# Driver_mosfet_v1_4.net
KiCad netlist of a schematic drawn in EAGLE
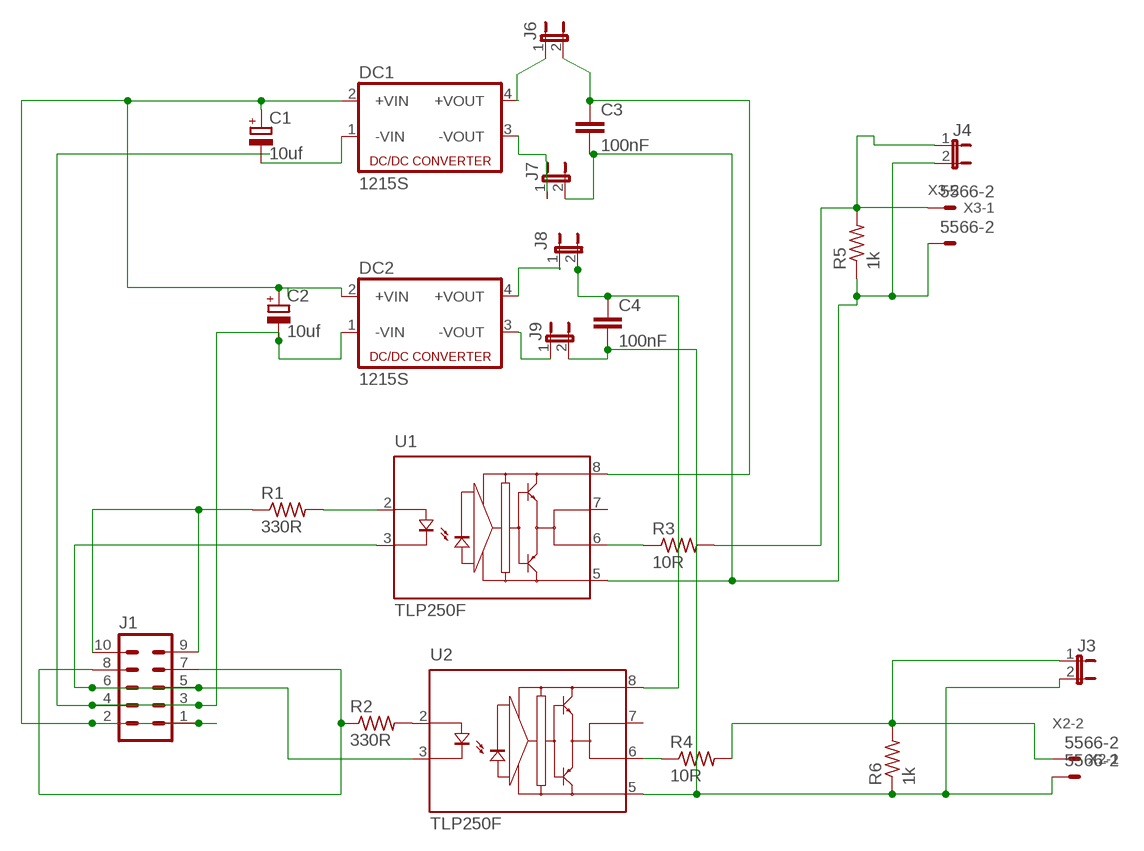
[diagram p0: schematic, sheet 1]

(export (version "E")
  (design (tool "Eeschema 10.0.6"))
  (components
    (comp (ref "C1")
      (value "10uf")
      (footprint "eagle-import:E2,5-6")
      (libsource (lib "eagle-import") (part "CPOL-EUE2.5-6"))
    )
    (comp (ref "C2")
      (value "10uf")
      (footprint "eagle-import:E2,5-6")
      (libsource (lib "eagle-import") (part "CPOL-EUE2.5-6"))
    )
    (comp (ref "C3")
      (value "100nF")
      (footprint "eagle-import:C5B3.5")
      (libsource (lib "eagle-import") (part "C5/3.5"))
    )
    (comp (ref "C4")
      (value "100nF")
      (footprint "eagle-import:C5B3.5")
      (libsource (lib "eagle-import") (part "C5/3.5"))
    )
    (comp (ref "DC1")
      (value "1215S")
      (footprint "eagle-import:4SIL")
      (libsource (lib "eagle-import") (part "VA-?S1.52409"))
    )
    (comp (ref "DC2")
      (value "1215S")
      (footprint "eagle-import:4SIL")
      (libsource (lib "eagle-import") (part "VA-?S1.52409"))
    )
    (comp (ref "J1")
      (value "MA05-2")
      (footprint "eagle-import:MA05-2")
      (libsource (lib "eagle-import") (part "MA05-2"))
    )
    (comp (ref "J3")
      (value "JP1E")
      (footprint "eagle-import:JP1")
      (libsource (lib "eagle-import") (part "JP1E"))
    )
    (comp (ref "J4")
      (value "JP1E")
      (footprint "eagle-import:JP1")
      (libsource (lib "eagle-import") (part "JP1E"))
    )
    (comp (ref "J6")
      (value "JP1E")
      (footprint "eagle-import:JP1")
      (libsource (lib "eagle-import") (part "JP1E"))
    )
    (comp (ref "J7")
      (value "JP1E")
      (footprint "eagle-import:JP1")
      (libsource (lib "eagle-import") (part "JP1E"))
    )
    (comp (ref "J8")
      (value "JP1E")
      (footprint "eagle-import:JP1")
      (libsource (lib "eagle-import") (part "JP1E"))
    )
    (comp (ref "J9")
      (value "JP1E")
      (footprint "eagle-import:JP1")
      (libsource (lib "eagle-import") (part "JP1E"))
    )
    (comp (ref "R1")
      (value "330R")
      (footprint "eagle-import:0309_12")
      (libsource (lib "eagle-import") (part "R-US_0309/12"))
    )
    (comp (ref "R2")
      (value "330R")
      (footprint "eagle-import:0309_12")
      (libsource (lib "eagle-import") (part "R-US_0309/12"))
    )
    (comp (ref "R3")
      (value "10R")
      (footprint "eagle-import:0309_12")
      (libsource (lib "eagle-import") (part "R-US_0309/12"))
    )
    (comp (ref "R4")
      (value "10R")
      (footprint "eagle-import:0309_12")
      (libsource (lib "eagle-import") (part "R-US_0309/12"))
    )
    (comp (ref "R5")
      (value "1k")
      (footprint "eagle-import:0309_12")
      (libsource (lib "eagle-import") (part "R-US_0309/12"))
    )
    (comp (ref "R6")
      (value "1k")
      (footprint "eagle-import:0309_12")
      (libsource (lib "eagle-import") (part "R-US_0309/12"))
    )
    (comp (ref "U1")
      (value "TLP250F")
      (footprint "eagle-import:DIL08")
      (libsource (lib "eagle-import") (part "TLP250F"))
    )
    (comp (ref "U2")
      (value "TLP250F")
      (footprint "eagle-import:DIL08")
      (libsource (lib "eagle-import") (part "TLP250F"))
    )
    (comp (ref "X2")
      (value "5566-2")
      (footprint "eagle-import:5566-2")
      (fields (field (name "MF") "MOLEX"))
      (libsource (lib "eagle-import") (part "5566-2"))
    )
    (comp (ref "X3")
      (value "5566-2")
      (footprint "eagle-import:5566-2")
      (fields (field (name "MF") "MOLEX"))
      (libsource (lib "eagle-import") (part "5566-2"))
    )
  )
  (nets
    (net (code "1") (name "/N$22") (class "Default")
      (node (ref "C1") (pin "-") (pinfunction "-_-") (pintype "passive"))
      (node (ref "C2") (pin "-") (pinfunction "-_-") (pintype "passive"))
      (node (ref "DC1") (pin "1") (pinfunction "-VIN_1") (pintype "passive"))
      (node (ref "DC2") (pin "1") (pinfunction "-VIN_1") (pintype "passive"))
      (node (ref "J1") (pin "3") (pinfunction "3_3") (pintype "passive"))
      (node (ref "J1") (pin "4") (pinfunction "4_4") (pintype "passive"))
    )
    (net (code "2") (name "Net-(DC1-+VIN)") (class "Default")
      (node (ref "C1") (pin "+") (pinfunction "+_+") (pintype "passive"))
      (node (ref "C2") (pin "+") (pinfunction "+_+") (pintype "passive"))
      (node (ref "DC1") (pin "2") (pinfunction "+VIN_2") (pintype "passive"))
      (node (ref "DC2") (pin "2") (pinfunction "+VIN_2") (pintype "passive"))
      (node (ref "J1") (pin "1") (pinfunction "1_1") (pintype "passive"))
      (node (ref "J1") (pin "2") (pinfunction "2_2") (pintype "passive"))
    )
    (net (code "3") (name "Net-(DC1-+VOUT)") (class "Default")
      (node (ref "DC1") (pin "4") (pinfunction "+VOUT_4") (pintype "passive"))
      (node (ref "J6") (pin "1") (pinfunction "1_1") (pintype "passive"))
    )
    (net (code "4") (name "Net-(DC1--VOUT)") (class "Default")
      (node (ref "DC1") (pin "3") (pinfunction "-VOUT_3") (pintype "passive"))
      (node (ref "J7") (pin "1") (pinfunction "1_1") (pintype "passive"))
    )
    (net (code "5") (name "Net-(DC2-+VOUT)") (class "Default")
      (node (ref "DC2") (pin "4") (pinfunction "+VOUT_4") (pintype "passive"))
      (node (ref "J8") (pin "1") (pinfunction "1_1") (pintype "passive"))
    )
    (net (code "6") (name "Net-(DC2--VOUT)") (class "Default")
      (node (ref "DC2") (pin "3") (pinfunction "-VOUT_3") (pintype "passive"))
      (node (ref "J9") (pin "1") (pinfunction "1_1") (pintype "passive"))
    )
    (net (code "7") (name "Net-(J1-Pad7)") (class "Default")
      (node (ref "J1") (pin "7") (pinfunction "7_7") (pintype "passive"))
      (node (ref "J1") (pin "8") (pinfunction "8_8") (pintype "passive"))
      (node (ref "R2") (pin "1") (pinfunction "1_1") (pintype "passive"))
    )
    (net (code "8") (name "Net-(J1-Pad10)") (class "Default")
      (node (ref "J1") (pin "10") (pinfunction "10_10") (pintype "passive"))
      (node (ref "J1") (pin "9") (pinfunction "9_9") (pintype "passive"))
      (node (ref "R1") (pin "1") (pinfunction "1_1") (pintype "passive"))
    )
    (net (code "9") (name "Net-(U1-A)") (class "Default")
      (node (ref "R1") (pin "2") (pinfunction "2_2") (pintype "passive"))
      (node (ref "U1") (pin "2") (pinfunction "A_2") (pintype "bidirectional"))
    )
    (net (code "10") (name "Net-(U1-GND)") (class "Default")
      (node (ref "C3") (pin "2") (pinfunction "2_2") (pintype "passive"))
      (node (ref "J4") (pin "2") (pinfunction "2_2") (pintype "passive"))
      (node (ref "J7") (pin "2") (pinfunction "2_2") (pintype "passive"))
      (node (ref "R5") (pin "1") (pinfunction "1_1") (pintype "passive"))
      (node (ref "U1") (pin "5") (pinfunction "GND_5") (pintype "bidirectional"))
      (node (ref "X3") (pin "2") (pinfunction "S_2") (pintype "passive"))
    )
    (net (code "11") (name "Net-(U1-K)") (class "Default")
      (node (ref "J1") (pin "5") (pinfunction "5_5") (pintype "passive"))
      (node (ref "J1") (pin "6") (pinfunction "6_6") (pintype "passive"))
      (node (ref "U1") (pin "3") (pinfunction "K_3") (pintype "bidirectional"))
      (node (ref "U2") (pin "3") (pinfunction "K_3") (pintype "bidirectional"))
    )
    (net (code "12") (name "Net-(U1-VCC)") (class "Default")
      (node (ref "C3") (pin "1") (pinfunction "1_1") (pintype "passive"))
      (node (ref "J6") (pin "2") (pinfunction "2_2") (pintype "passive"))
      (node (ref "U1") (pin "8") (pinfunction "VCC_8") (pintype "bidirectional"))
    )
    (net (code "13") (name "Net-(U1-VO)") (class "Default")
      (node (ref "R3") (pin "1") (pinfunction "1_1") (pintype "passive"))
      (node (ref "U1") (pin "6") (pinfunction "VO_6") (pintype "bidirectional"))
    )
    (net (code "14") (name "Net-(U2-A)") (class "Default")
      (node (ref "R2") (pin "2") (pinfunction "2_2") (pintype "passive"))
      (node (ref "U2") (pin "2") (pinfunction "A_2") (pintype "bidirectional"))
    )
    (net (code "15") (name "Net-(U2-GND)") (class "Default")
      (node (ref "C4") (pin "2") (pinfunction "2_2") (pintype "passive"))
      (node (ref "J3") (pin "2") (pinfunction "2_2") (pintype "passive"))
      (node (ref "J9") (pin "2") (pinfunction "2_2") (pintype "passive"))
      (node (ref "R6") (pin "1") (pinfunction "1_1") (pintype "passive"))
      (node (ref "U2") (pin "5") (pinfunction "GND_5") (pintype "bidirectional"))
      (node (ref "X2") (pin "2") (pinfunction "S_2") (pintype "passive"))
    )
    (net (code "16") (name "Net-(U2-VCC)") (class "Default")
      (node (ref "C4") (pin "1") (pinfunction "1_1") (pintype "passive"))
      (node (ref "J8") (pin "2") (pinfunction "2_2") (pintype "passive"))
      (node (ref "U2") (pin "8") (pinfunction "VCC_8") (pintype "bidirectional"))
    )
    (net (code "17") (name "Net-(U2-VO)") (class "Default")
      (node (ref "R4") (pin "1") (pinfunction "1_1") (pintype "passive"))
      (node (ref "U2") (pin "6") (pinfunction "VO_6") (pintype "bidirectional"))
    )
    (net (code "18") (name "Net-(X2A-S)") (class "Default")
      (node (ref "J3") (pin "1") (pinfunction "1_1") (pintype "passive"))
      (node (ref "R4") (pin "2") (pinfunction "2_2") (pintype "passive"))
      (node (ref "R6") (pin "2") (pinfunction "2_2") (pintype "passive"))
      (node (ref "X2") (pin "1") (pinfunction "S_1") (pintype "passive"))
    )
    (net (code "19") (name "Net-(X3A-S)") (class "Default")
      (node (ref "J4") (pin "1") (pinfunction "1_1") (pintype "passive"))
      (node (ref "R3") (pin "2") (pinfunction "2_2") (pintype "passive"))
      (node (ref "R5") (pin "2") (pinfunction "2_2") (pintype "passive"))
      (node (ref "X3") (pin "1") (pinfunction "S_1") (pintype "passive"))
    )
    (net (code "20") (name "unconnected-(U1-VO'-Pad7)") (class "Default")
      (node (ref "U1") (pin "7") (pinfunction "VO'_7") (pintype "bidirectional"))
    )
    (net (code "21") (name "unconnected-(U2-VO'-Pad7)") (class "Default")
      (node (ref "U2") (pin "7") (pinfunction "VO'_7") (pintype "bidirectional"))
    )
  )
)
